# EasyEDA_JamSoft_SI-1_2021-01-22.net
KiCad netlist of a schematic drawn in EasyEDA
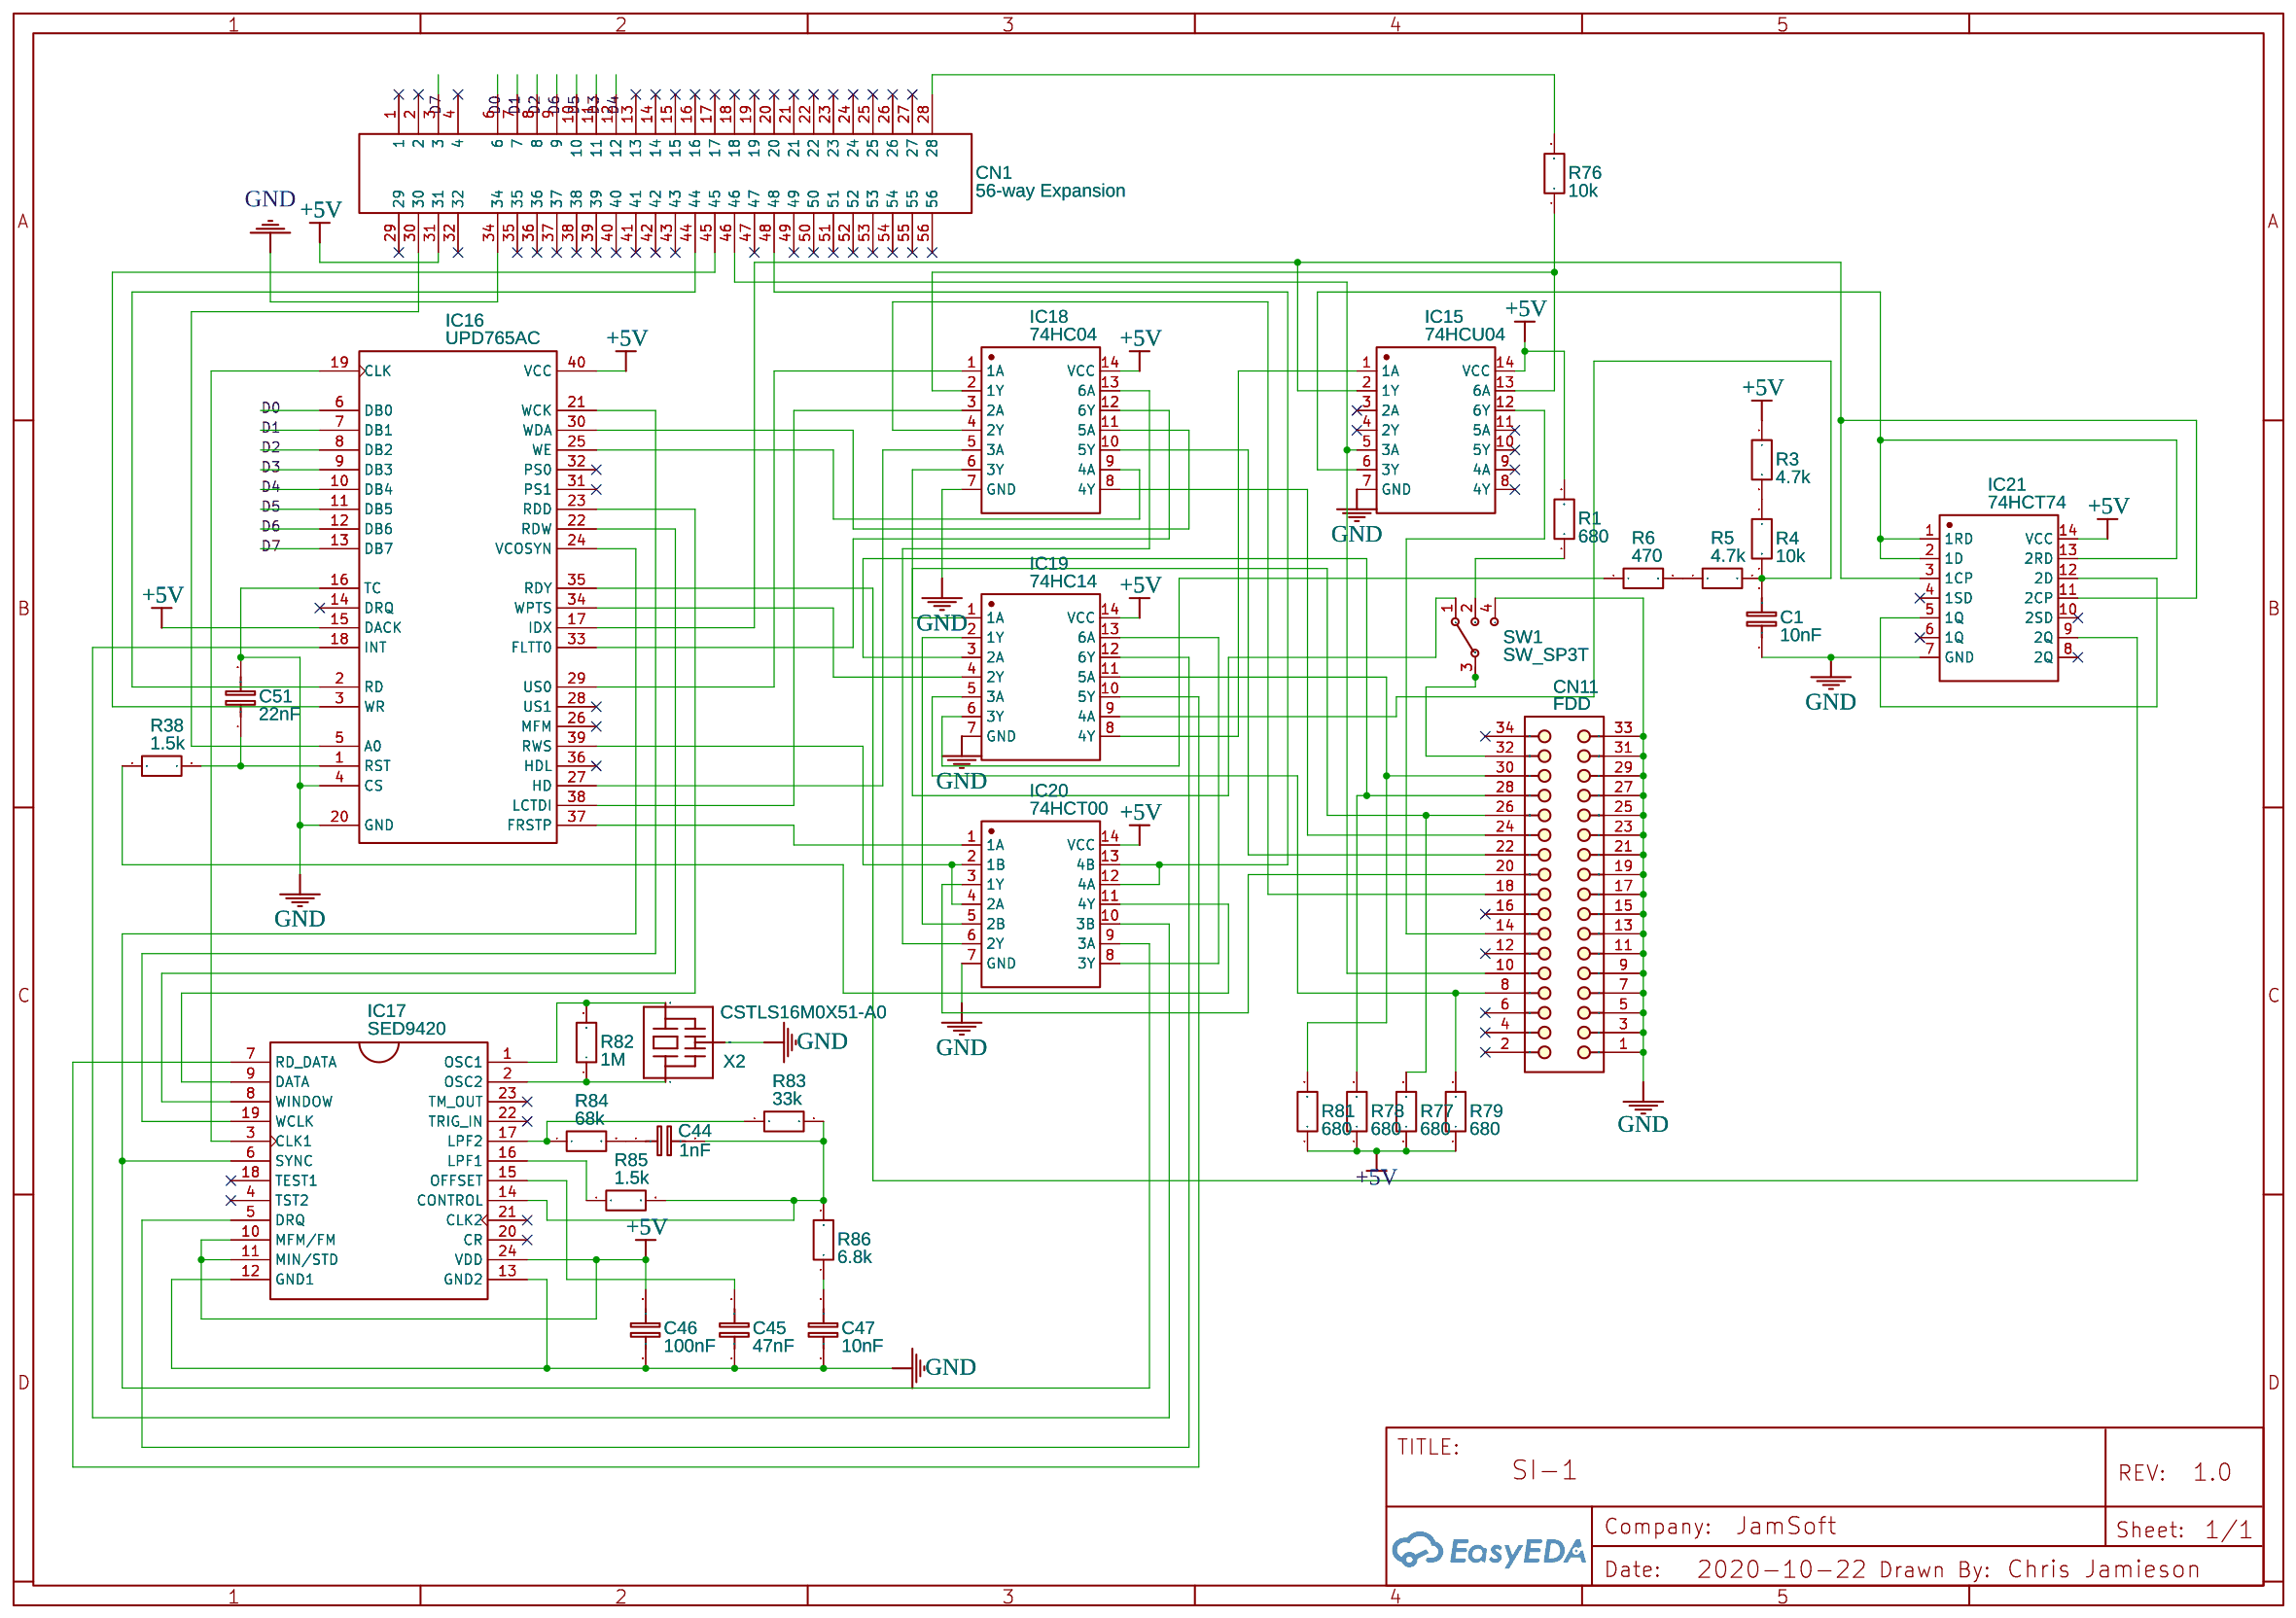
[diagram p0: schematic sheet]

(export (version "E")
  (design (tool "Eeschema 10.0.6"))
  (components
    (comp (ref "C1") (value "10nF") (libsource (lib "") (part "C_RAD-0.2_EU_2")))
    (comp (ref "C44") (value "1nF") (libsource (lib "") (part "C_RAD-0.2_EU")))
    (comp (ref "C45") (value "47nF") (libsource (lib "") (part "C_RAD-0.2_EU_1")))
    (comp (ref "C46") (value "100nF") (libsource (lib "") (part "C_RAD-0.2_EU_1")))
    (comp (ref "C47") (value "10nF") (libsource (lib "") (part "C_RAD-0.2_EU_1")))
    (comp (ref "C51") (value "22nF") (libsource (lib "") (part "C_RAD-0.2_EU_2")))
    (comp (ref "CN1") (value "56-way Expansion") (libsource (lib "") (part "56-way PCB Connector")))
    (comp (ref "CN11") (value "FDD") (libsource (lib "") (part "09 18 534 6914")))
    (comp (ref "IC15") (value "74HCU04") (libsource (lib "") (part "74HC04N,652")))
    (comp (ref "IC16") (value "UPD765AC") (libsource (lib "") (part "UPD765AC")))
    (comp (ref "IC17")
      (value "SED9420")
      (fields (field (name "BOM_Manufacturer Part") "SED9420CAC"))
      (libsource (lib "") (part "SED9420"))
    )
    (comp (ref "IC18") (value "74HC04") (libsource (lib "") (part "74HC04N,652")))
    (comp (ref "IC19") (value "74HC14") (libsource (lib "") (part "74HC14N,652")))
    (comp (ref "IC20") (value "74HCT00") (libsource (lib "") (part "74HCT00N")))
    (comp (ref "IC21") (value "74HCT74") (libsource (lib "") (part "74HCT74N")))
    (comp (ref "R1") (value "680") (libsource (lib "") (part "R_AXIAL-0.4_EU")))
    (comp (ref "R3") (value "4.7k") (libsource (lib "") (part "R_AXIAL-0.4_EU_2")))
    (comp (ref "R4") (value "10k") (libsource (lib "") (part "R_AXIAL-0.4_EU_2")))
    (comp (ref "R5") (value "4.7k") (libsource (lib "") (part "R_AXIAL-0.4_EU_1")))
    (comp (ref "R6") (value "470") (libsource (lib "") (part "R_AXIAL-0.4_EU_1")))
    (comp (ref "R38") (value "1.5k") (libsource (lib "") (part "R_AXIAL-0.4_EU_1")))
    (comp (ref "R76") (value "10k") (libsource (lib "") (part "R_AXIAL-0.4_EU")))
    (comp (ref "R77") (value "680") (libsource (lib "") (part "R_AXIAL-0.4_EU")))
    (comp (ref "R78") (value "680") (libsource (lib "") (part "R_AXIAL-0.4_EU")))
    (comp (ref "R79") (value "680") (libsource (lib "") (part "R_AXIAL-0.4_EU")))
    (comp (ref "R81") (value "680") (libsource (lib "") (part "R_AXIAL-0.4_EU")))
    (comp (ref "R82") (value "1M") (libsource (lib "") (part "R_AXIAL-0.6_EU")))
    (comp (ref "R83") (value "33k") (libsource (lib "") (part "R_AXIAL-0.4_EU_1")))
    (comp (ref "R84") (value "68k") (libsource (lib "") (part "R_AXIAL-0.4_EU_1")))
    (comp (ref "R85") (value "1.5k") (libsource (lib "") (part "R_AXIAL-0.4_EU_1")))
    (comp (ref "R86") (value "6.8k") (libsource (lib "") (part "R_AXIAL-0.4_EU")))
    (comp (ref "SW1") (value "SW_SP3T") (libsource (lib "") (part "SW_SP3T")))
    (comp (ref "X2") (value "CSTLS16M0X51-A0") (libsource (lib "") (part "CSTLS_X")))
  )
  (nets
    (net (code "1") (name "+5V") (class "Default")
      (node (ref "C46") (pin "2") (pinfunction "2_2") (pintype "unspecified"))
      (node (ref "CN1") (pin "31") (pinfunction "31_31") (pintype "unspecified"))
      (node (ref "IC15") (pin "14") (pinfunction "VCC_14") (pintype "unspecified"))
      (node (ref "IC16") (pin "15") (pinfunction "DACK_15") (pintype "unspecified"))
      (node (ref "IC16") (pin "40") (pinfunction "VCC_40") (pintype "passive"))
      (node (ref "IC17") (pin "10") (pinfunction "MFM/FM_10") (pintype "unspecified"))
      (node (ref "IC17") (pin "11") (pinfunction "MIN/STD_11") (pintype "unspecified"))
      (node (ref "IC17") (pin "24") (pinfunction "VDD_24") (pintype "passive"))
      (node (ref "IC18") (pin "14") (pinfunction "VCC_14") (pintype "unspecified"))
      (node (ref "IC19") (pin "14") (pinfunction "VCC_14") (pintype "unspecified"))
      (node (ref "IC20") (pin "14") (pinfunction "VCC_14") (pintype "unspecified"))
      (node (ref "IC21") (pin "14") (pinfunction "VCC_14") (pintype "unspecified"))
      (node (ref "R1") (pin "2") (pinfunction "2_2") (pintype "unspecified"))
      (node (ref "R3") (pin "1") (pinfunction "1_1") (pintype "unspecified"))
      (node (ref "R77") (pin "1") (pinfunction "1_1") (pintype "unspecified"))
      (node (ref "R78") (pin "1") (pinfunction "1_1") (pintype "unspecified"))
      (node (ref "R79") (pin "1") (pinfunction "1_1") (pintype "unspecified"))
      (node (ref "R81") (pin "1") (pinfunction "1_1") (pintype "unspecified"))
    )
    (net (code "2") (name "/D0") (class "Default")
      (node (ref "CN1") (pin "6") (pinfunction "6_6") (pintype "unspecified"))
      (node (ref "IC16") (pin "6") (pinfunction "DB0_6") (pintype "bidirectional"))
    )
    (net (code "3") (name "/D1") (class "Default")
      (node (ref "CN1") (pin "7") (pinfunction "7_7") (pintype "unspecified"))
      (node (ref "IC16") (pin "7") (pinfunction "DB1_7") (pintype "bidirectional"))
    )
    (net (code "4") (name "/D2") (class "Default")
      (node (ref "CN1") (pin "8") (pinfunction "8_8") (pintype "unspecified"))
      (node (ref "IC16") (pin "8") (pinfunction "DB2_8") (pintype "bidirectional"))
    )
    (net (code "5") (name "/D3") (class "Default")
      (node (ref "CN1") (pin "11") (pinfunction "11_11") (pintype "unspecified"))
      (node (ref "IC16") (pin "9") (pinfunction "DB3_9") (pintype "bidirectional"))
    )
    (net (code "6") (name "/D4") (class "Default")
      (node (ref "CN1") (pin "12") (pinfunction "12_12") (pintype "unspecified"))
      (node (ref "IC16") (pin "10") (pinfunction "DB4_10") (pintype "bidirectional"))
    )
    (net (code "7") (name "/D5") (class "Default")
      (node (ref "CN1") (pin "10") (pinfunction "10_10") (pintype "unspecified"))
      (node (ref "IC16") (pin "11") (pinfunction "DB5_11") (pintype "bidirectional"))
    )
    (net (code "8") (name "/D6") (class "Default")
      (node (ref "CN1") (pin "9") (pinfunction "9_9") (pintype "unspecified"))
      (node (ref "IC16") (pin "12") (pinfunction "DB6_12") (pintype "bidirectional"))
    )
    (net (code "9") (name "/D7") (class "Default")
      (node (ref "CN1") (pin "3") (pinfunction "3_3") (pintype "unspecified"))
      (node (ref "IC16") (pin "13") (pinfunction "DB7_13") (pintype "bidirectional"))
    )
    (net (code "10") (name "GND") (class "Default")
      (node (ref "C1") (pin "1") (pinfunction "1_1") (pintype "unspecified"))
      (node (ref "C45") (pin "1") (pinfunction "1_1") (pintype "unspecified"))
      (node (ref "C46") (pin "1") (pinfunction "1_1") (pintype "unspecified"))
      (node (ref "C47") (pin "1") (pinfunction "1_1") (pintype "unspecified"))
      (node (ref "C51") (pin "2") (pinfunction "2_2") (pintype "unspecified"))
      (node (ref "CN1") (pin "34") (pinfunction "34_34") (pintype "unspecified"))
      (node (ref "CN11") (pin "1") (pinfunction "1_1") (pintype "unspecified"))
      (node (ref "CN11") (pin "11") (pinfunction "11_11") (pintype "unspecified"))
      (node (ref "CN11") (pin "13") (pinfunction "13_13") (pintype "unspecified"))
      (node (ref "CN11") (pin "15") (pinfunction "15_15") (pintype "unspecified"))
      (node (ref "CN11") (pin "17") (pinfunction "17_17") (pintype "unspecified"))
      (node (ref "CN11") (pin "19") (pinfunction "19_19") (pintype "unspecified"))
      (node (ref "CN11") (pin "21") (pinfunction "21_21") (pintype "unspecified"))
      (node (ref "CN11") (pin "23") (pinfunction "23_23") (pintype "unspecified"))
      (node (ref "CN11") (pin "25") (pinfunction "25_25") (pintype "unspecified"))
      (node (ref "CN11") (pin "27") (pinfunction "27_27") (pintype "unspecified"))
      (node (ref "CN11") (pin "29") (pinfunction "29_29") (pintype "unspecified"))
      (node (ref "CN11") (pin "3") (pinfunction "3_3") (pintype "unspecified"))
      (node (ref "CN11") (pin "31") (pinfunction "31_31") (pintype "unspecified"))
      (node (ref "CN11") (pin "33") (pinfunction "33_33") (pintype "unspecified"))
      (node (ref "CN11") (pin "5") (pinfunction "5_5") (pintype "unspecified"))
      (node (ref "CN11") (pin "7") (pinfunction "7_7") (pintype "unspecified"))
      (node (ref "CN11") (pin "9") (pinfunction "9_9") (pintype "unspecified"))
      (node (ref "IC15") (pin "7") (pinfunction "GND_7") (pintype "unspecified"))
      (node (ref "IC16") (pin "16") (pinfunction "TC_16") (pintype "unspecified"))
      (node (ref "IC16") (pin "20") (pinfunction "GND_20") (pintype "passive"))
      (node (ref "IC16") (pin "4") (pinfunction "CS_4") (pintype "unspecified"))
      (node (ref "IC17") (pin "12") (pinfunction "GND1_12") (pintype "passive"))
      (node (ref "IC17") (pin "13") (pinfunction "GND2_13") (pintype "passive"))
      (node (ref "IC18") (pin "7") (pinfunction "GND_7") (pintype "unspecified"))
      (node (ref "IC19") (pin "7") (pinfunction "GND_7") (pintype "unspecified"))
      (node (ref "IC20") (pin "7") (pinfunction "GND_7") (pintype "unspecified"))
      (node (ref "IC21") (pin "7") (pinfunction "GND_7") (pintype "unspecified"))
      (node (ref "SW1") (pin "4") (pinfunction "4_4") (pintype "unspecified"))
      (node (ref "X2") (pin "2") (pinfunction "VSS_2") (pintype "passive"))
    )
    (net (code "11") (name "Net-(C44-Pad1)") (class "Default")
      (node (ref "C44") (pin "1") (pinfunction "1_1") (pintype "unspecified"))
      (node (ref "R84") (pin "2") (pinfunction "2_2") (pintype "unspecified"))
    )
    (net (code "12") (name "Net-(C47-Pad2)") (class "Default")
      (node (ref "C47") (pin "2") (pinfunction "2_2") (pintype "unspecified"))
      (node (ref "R86") (pin "1") (pinfunction "1_1") (pintype "unspecified"))
    )
    (net (code "13") (name "Net-(CN1-Pad28)") (class "Default")
      (node (ref "CN1") (pin "28") (pinfunction "28_28") (pintype "unspecified"))
      (node (ref "R76") (pin "2") (pinfunction "2_2") (pintype "unspecified"))
    )
    (net (code "14") (name "Net-(CN11-Pad32)") (class "Default")
      (node (ref "CN11") (pin "32") (pinfunction "32_32") (pintype "unspecified"))
      (node (ref "SW1") (pin "3") (pinfunction "3_3") (pintype "unspecified"))
    )
    (net (code "15") (name "Net-(IC15-1A)") (class "Default")
      (node (ref "IC15") (pin "1") (pinfunction "1A_1") (pintype "unspecified"))
      (node (ref "IC19") (pin "8") (pinfunction "4Y_8") (pintype "unspecified"))
    )
    (net (code "16") (name "Net-(IC15-1Y)") (class "Default")
      (node (ref "IC15") (pin "2") (pinfunction "1Y_2") (pintype "unspecified"))
      (node (ref "IC16") (pin "17") (pinfunction "IDX_17") (pintype "unspecified"))
      (node (ref "IC21") (pin "11") (pinfunction "2CP_11") (pintype "unspecified"))
      (node (ref "IC21") (pin "3") (pinfunction "1CP_3") (pintype "unspecified"))
    )
    (net (code "17") (name "Net-(IC15-3A)") (class "Default")
      (node (ref "CN1") (pin "46") (pinfunction "46_46") (pintype "unspecified"))
      (node (ref "CN11") (pin "10") (pinfunction "10_10") (pintype "unspecified"))
      (node (ref "IC15") (pin "5") (pinfunction "3A_5") (pintype "unspecified"))
    )
    (net (code "18") (name "Net-(IC15-3Y)") (class "Default")
      (node (ref "IC15") (pin "6") (pinfunction "3Y_6") (pintype "unspecified"))
      (node (ref "IC21") (pin "1") (pinfunction "1RD_1") (pintype "unspecified"))
      (node (ref "IC21") (pin "13") (pinfunction "2RD_13") (pintype "unspecified"))
      (node (ref "IC21") (pin "2") (pinfunction "1D_2") (pintype "unspecified"))
    )
    (net (code "19") (name "Net-(IC15-6A)") (class "Default")
      (node (ref "IC15") (pin "13") (pinfunction "6A_13") (pintype "unspecified"))
      (node (ref "IC18") (pin "2") (pinfunction "1Y_2") (pintype "unspecified"))
      (node (ref "R76") (pin "1") (pinfunction "1_1") (pintype "unspecified"))
    )
    (net (code "20") (name "Net-(IC15-6Y)") (class "Default")
      (node (ref "CN11") (pin "14") (pinfunction "14_14") (pintype "unspecified"))
      (node (ref "IC15") (pin "12") (pinfunction "6Y_12") (pintype "unspecified"))
    )
    (net (code "21") (name "Net-(IC16-A0)") (class "Default")
      (node (ref "CN1") (pin "30") (pinfunction "30_30") (pintype "unspecified"))
      (node (ref "IC16") (pin "5") (pinfunction "A0_5") (pintype "unspecified"))
    )
    (net (code "22") (name "Net-(IC16-CLK)") (class "Default")
      (node (ref "IC16") (pin "19") (pinfunction "CLK_19") (pintype "unspecified"))
      (node (ref "IC17") (pin "3") (pinfunction "CLK1_3") (pintype "unspecified"))
    )
    (net (code "23") (name "Net-(IC16-FLTT0)") (class "Default")
      (node (ref "IC16") (pin "33") (pinfunction "FLTT0_33") (pintype "unspecified"))
      (node (ref "IC18") (pin "12") (pinfunction "6Y_12") (pintype "unspecified"))
    )
    (net (code "24") (name "Net-(IC16-FRSTP)") (class "Default")
      (node (ref "IC16") (pin "37") (pinfunction "FRSTP_37") (pintype "output"))
      (node (ref "IC20") (pin "1") (pinfunction "1A_1") (pintype "unspecified"))
    )
    (net (code "25") (name "Net-(IC16-HD)") (class "Default")
      (node (ref "IC16") (pin "27") (pinfunction "HD_27") (pintype "output"))
      (node (ref "IC18") (pin "5") (pinfunction "3A_5") (pintype "unspecified"))
    )
    (net (code "26") (name "Net-(IC16-INT)") (class "Default")
      (node (ref "IC16") (pin "18") (pinfunction "INT_18") (pintype "output"))
      (node (ref "IC20") (pin "10") (pinfunction "3B_10") (pintype "unspecified"))
    )
    (net (code "27") (name "Net-(IC16-LCTDI)") (class "Default")
      (node (ref "IC16") (pin "38") (pinfunction "LCTDI_38") (pintype "output"))
      (node (ref "IC18") (pin "3") (pinfunction "2A_3") (pintype "unspecified"))
    )
    (net (code "28") (name "Net-(IC16-RD)") (class "Default")
      (node (ref "CN1") (pin "44") (pinfunction "44_44") (pintype "unspecified"))
      (node (ref "IC16") (pin "2") (pinfunction "RD_2") (pintype "unspecified"))
    )
    (net (code "29") (name "Net-(IC16-RDD)") (class "Default")
      (node (ref "IC16") (pin "23") (pinfunction "RDD_23") (pintype "unspecified"))
      (node (ref "IC17") (pin "9") (pinfunction "DATA_9") (pintype "unspecified"))
    )
    (net (code "30") (name "Net-(IC16-RDW)") (class "Default")
      (node (ref "IC16") (pin "22") (pinfunction "RDW_22") (pintype "unspecified"))
      (node (ref "IC17") (pin "8") (pinfunction "WINDOW_8") (pintype "unspecified"))
    )
    (net (code "31") (name "Net-(IC16-RDY)") (class "Default")
      (node (ref "IC16") (pin "35") (pinfunction "RDY_35") (pintype "unspecified"))
      (node (ref "IC21") (pin "9") (pinfunction "2Q_9") (pintype "unspecified"))
    )
    (net (code "32") (name "Net-(IC16-RST)") (class "Default")
      (node (ref "C51") (pin "1") (pinfunction "1_1") (pintype "unspecified"))
      (node (ref "IC16") (pin "1") (pinfunction "RST_1") (pintype "unspecified"))
      (node (ref "R38") (pin "2") (pinfunction "2_2") (pintype "unspecified"))
    )
    (net (code "33") (name "Net-(IC16-RWS)") (class "Default")
      (node (ref "IC16") (pin "39") (pinfunction "RWS_39") (pintype "output"))
      (node (ref "IC20") (pin "2") (pinfunction "1B_2") (pintype "unspecified"))
      (node (ref "IC20") (pin "4") (pinfunction "2A_4") (pintype "unspecified"))
    )
    (net (code "34") (name "Net-(IC16-US0)") (class "Default")
      (node (ref "IC16") (pin "29") (pinfunction "US0_29") (pintype "output"))
      (node (ref "IC18") (pin "1") (pinfunction "1A_1") (pintype "unspecified"))
    )
    (net (code "35") (name "Net-(IC16-VCOSYN)") (class "Default")
      (node (ref "IC16") (pin "24") (pinfunction "VCOSYN_24") (pintype "output"))
      (node (ref "IC17") (pin "6") (pinfunction "SYNC_6") (pintype "unspecified"))
      (node (ref "IC20") (pin "9") (pinfunction "3A_9") (pintype "unspecified"))
    )
    (net (code "36") (name "Net-(IC16-WCK)") (class "Default")
      (node (ref "IC16") (pin "21") (pinfunction "WCK_21") (pintype "unspecified"))
      (node (ref "IC17") (pin "19") (pinfunction "WCLK_19") (pintype "unspecified"))
    )
    (net (code "37") (name "Net-(IC16-WDA)") (class "Default")
      (node (ref "IC16") (pin "30") (pinfunction "WDA_30") (pintype "output"))
      (node (ref "IC18") (pin "11") (pinfunction "5A_11") (pintype "unspecified"))
    )
    (net (code "38") (name "Net-(IC16-WE)") (class "Default")
      (node (ref "IC16") (pin "25") (pinfunction "WE_25") (pintype "output"))
      (node (ref "IC18") (pin "9") (pinfunction "4A_9") (pintype "unspecified"))
    )
    (net (code "39") (name "Net-(IC16-WPTS)") (class "Default")
      (node (ref "IC16") (pin "34") (pinfunction "WPTS_34") (pintype "unspecified"))
      (node (ref "IC19") (pin "4") (pinfunction "2Y_4") (pintype "unspecified"))
    )
    (net (code "40") (name "Net-(IC16-WR)") (class "Default")
      (node (ref "CN1") (pin "45") (pinfunction "45_45") (pintype "unspecified"))
      (node (ref "IC16") (pin "3") (pinfunction "WR_3") (pintype "unspecified"))
    )
    (net (code "41") (name "Net-(IC17-CONTROL)") (class "Default")
      (node (ref "C44") (pin "2") (pinfunction "2_2") (pintype "unspecified"))
      (node (ref "IC17") (pin "14") (pinfunction "CONTROL_14") (pintype "unspecified"))
      (node (ref "R83") (pin "2") (pinfunction "2_2") (pintype "unspecified"))
      (node (ref "R85") (pin "2") (pinfunction "2_2") (pintype "unspecified"))
      (node (ref "R86") (pin "2") (pinfunction "2_2") (pintype "unspecified"))
    )
    (net (code "42") (name "Net-(IC17-DRQ)") (class "Default")
      (node (ref "IC17") (pin "5") (pinfunction "DRQ_5") (pintype "unspecified"))
      (node (ref "IC19") (pin "12") (pinfunction "6Y_12") (pintype "unspecified"))
    )
    (net (code "43") (name "Net-(IC17-LPF1)") (class "Default")
      (node (ref "IC17") (pin "16") (pinfunction "LPF1_16") (pintype "unspecified"))
      (node (ref "R85") (pin "1") (pinfunction "1_1") (pintype "unspecified"))
    )
    (net (code "44") (name "Net-(IC17-LPF2)") (class "Default")
      (node (ref "IC17") (pin "17") (pinfunction "LPF2_17") (pintype "unspecified"))
      (node (ref "R83") (pin "1") (pinfunction "1_1") (pintype "unspecified"))
      (node (ref "R84") (pin "1") (pinfunction "1_1") (pintype "unspecified"))
    )
    (net (code "45") (name "Net-(IC17-OFFSET)") (class "Default")
      (node (ref "C45") (pin "2") (pinfunction "2_2") (pintype "unspecified"))
      (node (ref "IC17") (pin "15") (pinfunction "OFFSET_15") (pintype "unspecified"))
    )
    (net (code "46") (name "Net-(IC17-OSC1)") (class "Default")
      (node (ref "IC17") (pin "1") (pinfunction "OSC1_1") (pintype "unspecified"))
      (node (ref "R82") (pin "2") (pinfunction "2_2") (pintype "unspecified"))
      (node (ref "X2") (pin "3") (pinfunction "3_3") (pintype "input"))
    )
    (net (code "47") (name "Net-(IC17-OSC2)") (class "Default")
      (node (ref "IC17") (pin "2") (pinfunction "OSC2_2") (pintype "unspecified"))
      (node (ref "R82") (pin "1") (pinfunction "1_1") (pintype "unspecified"))
      (node (ref "X2") (pin "1") (pinfunction "1_1") (pintype "output"))
    )
    (net (code "48") (name "Net-(IC17-RD_DATA)") (class "Default")
      (node (ref "IC17") (pin "7") (pinfunction "RD_DATA_7") (pintype "unspecified"))
      (node (ref "IC19") (pin "10") (pinfunction "5Y_10") (pintype "unspecified"))
    )
    (net (code "49") (name "Net-(IC18-2Y)") (class "Default")
      (node (ref "CN11") (pin "18") (pinfunction "18_18") (pintype "unspecified"))
      (node (ref "IC18") (pin "4") (pinfunction "2Y_4") (pintype "unspecified"))
    )
    (net (code "50") (name "Net-(IC18-3Y)") (class "Default")
      (node (ref "IC18") (pin "6") (pinfunction "3Y_6") (pintype "unspecified"))
      (node (ref "SW1") (pin "1") (pinfunction "1_1") (pintype "unspecified"))
    )
    (net (code "51") (name "Net-(IC18-4Y)") (class "Default")
      (node (ref "CN11") (pin "24") (pinfunction "24_24") (pintype "unspecified"))
      (node (ref "IC18") (pin "8") (pinfunction "4Y_8") (pintype "unspecified"))
    )
    (net (code "52") (name "Net-(IC18-5Y)") (class "Default")
      (node (ref "CN11") (pin "22") (pinfunction "22_22") (pintype "unspecified"))
      (node (ref "IC18") (pin "10") (pinfunction "5Y_10") (pintype "unspecified"))
    )
    (net (code "53") (name "Net-(IC18-6A)") (class "Default")
      (node (ref "IC18") (pin "13") (pinfunction "6A_13") (pintype "unspecified"))
      (node (ref "IC20") (pin "6") (pinfunction "2Y_6") (pintype "unspecified"))
    )
    (net (code "54") (name "Net-(IC19-1A)") (class "Default")
      (node (ref "CN11") (pin "26") (pinfunction "26_26") (pintype "unspecified"))
      (node (ref "IC19") (pin "1") (pinfunction "1A_1") (pintype "unspecified"))
      (node (ref "R77") (pin "2") (pinfunction "2_2") (pintype "unspecified"))
    )
    (net (code "55") (name "Net-(IC19-1Y)") (class "Default")
      (node (ref "IC19") (pin "2") (pinfunction "1Y_2") (pintype "unspecified"))
      (node (ref "IC20") (pin "5") (pinfunction "2B_5") (pintype "unspecified"))
    )
    (net (code "56") (name "Net-(IC19-2A)") (class "Default")
      (node (ref "CN11") (pin "28") (pinfunction "28_28") (pintype "unspecified"))
      (node (ref "IC19") (pin "3") (pinfunction "2A_3") (pintype "unspecified"))
      (node (ref "R78") (pin "2") (pinfunction "2_2") (pintype "unspecified"))
    )
    (net (code "57") (name "Net-(IC19-3A)") (class "Default")
      (node (ref "CN11") (pin "8") (pinfunction "8_8") (pintype "unspecified"))
      (node (ref "IC19") (pin "5") (pinfunction "3A_5") (pintype "unspecified"))
      (node (ref "R79") (pin "2") (pinfunction "2_2") (pintype "unspecified"))
    )
    (net (code "58") (name "Net-(IC19-3Y)") (class "Default")
      (node (ref "IC19") (pin "6") (pinfunction "3Y_6") (pintype "unspecified"))
      (node (ref "R6") (pin "1") (pinfunction "1_1") (pintype "unspecified"))
    )
    (net (code "59") (name "Net-(IC19-4A)") (class "Default")
      (node (ref "C1") (pin "2") (pinfunction "2_2") (pintype "unspecified"))
      (node (ref "IC19") (pin "9") (pinfunction "4A_9") (pintype "unspecified"))
      (node (ref "R4") (pin "2") (pinfunction "2_2") (pintype "unspecified"))
      (node (ref "R5") (pin "2") (pinfunction "2_2") (pintype "unspecified"))
    )
    (net (code "60") (name "Net-(IC19-5A)") (class "Default")
      (node (ref "CN11") (pin "30") (pinfunction "30_30") (pintype "unspecified"))
      (node (ref "IC19") (pin "11") (pinfunction "5A_11") (pintype "unspecified"))
      (node (ref "R81") (pin "2") (pinfunction "2_2") (pintype "unspecified"))
    )
    (net (code "61") (name "Net-(IC19-6A)") (class "Default")
      (node (ref "IC19") (pin "13") (pinfunction "6A_13") (pintype "unspecified"))
      (node (ref "IC20") (pin "8") (pinfunction "3Y_8") (pintype "unspecified"))
    )
    (net (code "62") (name "Net-(IC20-1Y)") (class "Default")
      (node (ref "CN11") (pin "20") (pinfunction "20_20") (pintype "unspecified"))
      (node (ref "IC20") (pin "3") (pinfunction "1Y_3") (pintype "unspecified"))
    )
    (net (code "63") (name "Net-(IC20-4A)") (class "Default")
      (node (ref "CN1") (pin "48") (pinfunction "48_48") (pintype "unspecified"))
      (node (ref "IC20") (pin "12") (pinfunction "4A_12") (pintype "unspecified"))
      (node (ref "IC20") (pin "13") (pinfunction "4B_13") (pintype "unspecified"))
    )
    (net (code "64") (name "Net-(IC20-4Y)") (class "Default")
      (node (ref "IC20") (pin "11") (pinfunction "4Y_11") (pintype "unspecified"))
      (node (ref "R38") (pin "1") (pinfunction "1_1") (pintype "unspecified"))
    )
    (net (code "65") (name "Net-(IC21-2D)") (class "Default")
      (node (ref "IC21") (pin "12") (pinfunction "2D_12") (pintype "unspecified"))
      (node (ref "IC21") (pin "5") (pinfunction "1Q_5") (pintype "unspecified"))
    )
    (net (code "66") (name "Net-(R1-Pad1)") (class "Default")
      (node (ref "R1") (pin "1") (pinfunction "1_1") (pintype "unspecified"))
      (node (ref "SW1") (pin "2") (pinfunction "2_2") (pintype "unspecified"))
    )
    (net (code "67") (name "Net-(R3-Pad2)") (class "Default")
      (node (ref "R3") (pin "2") (pinfunction "2_2") (pintype "unspecified"))
      (node (ref "R4") (pin "1") (pinfunction "1_1") (pintype "unspecified"))
    )
    (net (code "68") (name "Net-(R5-Pad1)") (class "Default")
      (node (ref "R5") (pin "1") (pinfunction "1_1") (pintype "unspecified"))
      (node (ref "R6") (pin "2") (pinfunction "2_2") (pintype "unspecified"))
    )
    (net (code "69") (name "unconnected-(CN1-Pad1)") (class "Default")
      (node (ref "CN1") (pin "1") (pinfunction "1_1") (pintype "unspecified+no_connect"))
    )
    (net (code "70") (name "unconnected-(CN1-Pad2)") (class "Default")
      (node (ref "CN1") (pin "2") (pinfunction "2_2") (pintype "unspecified+no_connect"))
    )
    (net (code "71") (name "unconnected-(CN1-Pad4)") (class "Default")
      (node (ref "CN1") (pin "4") (pinfunction "4_4") (pintype "unspecified+no_connect"))
    )
    (net (code "72") (name "unconnected-(CN1-Pad13)") (class "Default")
      (node (ref "CN1") (pin "13") (pinfunction "13_13") (pintype "unspecified+no_connect"))
    )
    (net (code "73") (name "unconnected-(CN1-Pad14)") (class "Default")
      (node (ref "CN1") (pin "14") (pinfunction "14_14") (pintype "unspecified+no_connect"))
    )
    (net (code "74") (name "unconnected-(CN1-Pad15)") (class "Default")
      (node (ref "CN1") (pin "15") (pinfunction "15_15") (pintype "unspecified+no_connect"))
    )
    (net (code "75") (name "unconnected-(CN1-Pad16)") (class "Default")
      (node (ref "CN1") (pin "16") (pinfunction "16_16") (pintype "unspecified+no_connect"))
    )
    (net (code "76") (name "unconnected-(CN1-Pad17)") (class "Default")
      (node (ref "CN1") (pin "17") (pinfunction "17_17") (pintype "unspecified+no_connect"))
    )
    (net (code "77") (name "unconnected-(CN1-Pad18)") (class "Default")
      (node (ref "CN1") (pin "18") (pinfunction "18_18") (pintype "unspecified+no_connect"))
    )
    (net (code "78") (name "unconnected-(CN1-Pad19)") (class "Default")
      (node (ref "CN1") (pin "19") (pinfunction "19_19") (pintype "unspecified+no_connect"))
    )
    (net (code "79") (name "unconnected-(CN1-Pad20)") (class "Default")
      (node (ref "CN1") (pin "20") (pinfunction "20_20") (pintype "unspecified+no_connect"))
    )
    (net (code "80") (name "unconnected-(CN1-Pad21)") (class "Default")
      (node (ref "CN1") (pin "21") (pinfunction "21_21") (pintype "unspecified+no_connect"))
    )
    (net (code "81") (name "unconnected-(CN1-Pad22)") (class "Default")
      (node (ref "CN1") (pin "22") (pinfunction "22_22") (pintype "unspecified+no_connect"))
    )
    (net (code "82") (name "unconnected-(CN1-Pad23)") (class "Default")
      (node (ref "CN1") (pin "23") (pinfunction "23_23") (pintype "unspecified+no_connect"))
    )
    (net (code "83") (name "unconnected-(CN1-Pad24)") (class "Default")
      (node (ref "CN1") (pin "24") (pinfunction "24_24") (pintype "unspecified+no_connect"))
    )
    (net (code "84") (name "unconnected-(CN1-Pad25)") (class "Default")
      (node (ref "CN1") (pin "25") (pinfunction "25_25") (pintype "unspecified+no_connect"))
    )
    (net (code "85") (name "unconnected-(CN1-Pad26)") (class "Default")
      (node (ref "CN1") (pin "26") (pinfunction "26_26") (pintype "unspecified+no_connect"))
    )
    (net (code "86") (name "unconnected-(CN1-Pad27)") (class "Default")
      (node (ref "CN1") (pin "27") (pinfunction "27_27") (pintype "unspecified+no_connect"))
    )
    (net (code "87") (name "unconnected-(CN1-Pad29)") (class "Default")
      (node (ref "CN1") (pin "29") (pinfunction "29_29") (pintype "unspecified+no_connect"))
    )
    (net (code "88") (name "unconnected-(CN1-Pad32)") (class "Default")
      (node (ref "CN1") (pin "32") (pinfunction "32_32") (pintype "unspecified+no_connect"))
    )
    (net (code "89") (name "unconnected-(CN1-Pad35)") (class "Default")
      (node (ref "CN1") (pin "35") (pinfunction "35_35") (pintype "unspecified+no_connect"))
    )
    (net (code "90") (name "unconnected-(CN1-Pad36)") (class "Default")
      (node (ref "CN1") (pin "36") (pinfunction "36_36") (pintype "unspecified+no_connect"))
    )
    (net (code "91") (name "unconnected-(CN1-Pad37)") (class "Default")
      (node (ref "CN1") (pin "37") (pinfunction "37_37") (pintype "unspecified+no_connect"))
    )
    (net (code "92") (name "unconnected-(CN1-Pad38)") (class "Default")
      (node (ref "CN1") (pin "38") (pinfunction "38_38") (pintype "unspecified+no_connect"))
    )
    (net (code "93") (name "unconnected-(CN1-Pad39)") (class "Default")
      (node (ref "CN1") (pin "39") (pinfunction "39_39") (pintype "unspecified+no_connect"))
    )
    (net (code "94") (name "unconnected-(CN1-Pad40)") (class "Default")
      (node (ref "CN1") (pin "40") (pinfunction "40_40") (pintype "unspecified+no_connect"))
    )
    (net (code "95") (name "unconnected-(CN1-Pad41)") (class "Default")
      (node (ref "CN1") (pin "41") (pinfunction "41_41") (pintype "unspecified+no_connect"))
    )
    (net (code "96") (name "unconnected-(CN1-Pad42)") (class "Default")
      (node (ref "CN1") (pin "42") (pinfunction "42_42") (pintype "unspecified+no_connect"))
    )
    (net (code "97") (name "unconnected-(CN1-Pad43)") (class "Default")
      (node (ref "CN1") (pin "43") (pinfunction "43_43") (pintype "unspecified+no_connect"))
    )
    (net (code "98") (name "unconnected-(CN1-Pad47)") (class "Default")
      (node (ref "CN1") (pin "47") (pinfunction "47_47") (pintype "unspecified+no_connect"))
    )
    (net (code "99") (name "unconnected-(CN1-Pad49)") (class "Default")
      (node (ref "CN1") (pin "49") (pinfunction "49_49") (pintype "unspecified+no_connect"))
    )
    (net (code "100") (name "unconnected-(CN1-Pad50)") (class "Default")
      (node (ref "CN1") (pin "50") (pinfunction "50_50") (pintype "unspecified+no_connect"))
    )
    (net (code "101") (name "unconnected-(CN1-Pad51)") (class "Default")
      (node (ref "CN1") (pin "51") (pinfunction "51_51") (pintype "unspecified+no_connect"))
    )
    (net (code "102") (name "unconnected-(CN1-Pad52)") (class "Default")
      (node (ref "CN1") (pin "52") (pinfunction "52_52") (pintype "unspecified+no_connect"))
    )
    (net (code "103") (name "unconnected-(CN1-Pad53)") (class "Default")
      (node (ref "CN1") (pin "53") (pinfunction "53_53") (pintype "unspecified+no_connect"))
    )
    (net (code "104") (name "unconnected-(CN1-Pad54)") (class "Default")
      (node (ref "CN1") (pin "54") (pinfunction "54_54") (pintype "unspecified+no_connect"))
    )
    (net (code "105") (name "unconnected-(CN1-Pad55)") (class "Default")
      (node (ref "CN1") (pin "55") (pinfunction "55_55") (pintype "unspecified+no_connect"))
    )
    (net (code "106") (name "unconnected-(CN1-Pad56)") (class "Default")
      (node (ref "CN1") (pin "56") (pinfunction "56_56") (pintype "unspecified+no_connect"))
    )
    (net (code "107") (name "unconnected-(CN11-Pad2)") (class "Default")
      (node (ref "CN11") (pin "2") (pinfunction "2_2") (pintype "unspecified+no_connect"))
    )
    (net (code "108") (name "unconnected-(CN11-Pad4)") (class "Default")
      (node (ref "CN11") (pin "4") (pinfunction "4_4") (pintype "unspecified+no_connect"))
    )
    (net (code "109") (name "unconnected-(CN11-Pad6)") (class "Default")
      (node (ref "CN11") (pin "6") (pinfunction "6_6") (pintype "unspecified+no_connect"))
    )
    (net (code "110") (name "unconnected-(CN11-Pad12)") (class "Default")
      (node (ref "CN11") (pin "12") (pinfunction "12_12") (pintype "unspecified+no_connect"))
    )
    (net (code "111") (name "unconnected-(CN11-Pad16)") (class "Default")
      (node (ref "CN11") (pin "16") (pinfunction "16_16") (pintype "unspecified+no_connect"))
    )
    (net (code "112") (name "unconnected-(CN11-Pad34)") (class "Default")
      (node (ref "CN11") (pin "34") (pinfunction "34_34") (pintype "unspecified+no_connect"))
    )
    (net (code "113") (name "unconnected-(IC15-2A-Pad3)") (class "Default")
      (node (ref "IC15") (pin "3") (pinfunction "2A_3") (pintype "unspecified+no_connect"))
    )
    (net (code "114") (name "unconnected-(IC15-2Y-Pad4)") (class "Default")
      (node (ref "IC15") (pin "4") (pinfunction "2Y_4") (pintype "unspecified+no_connect"))
    )
    (net (code "115") (name "unconnected-(IC15-4A-Pad9)") (class "Default")
      (node (ref "IC15") (pin "9") (pinfunction "4A_9") (pintype "unspecified+no_connect"))
    )
    (net (code "116") (name "unconnected-(IC15-4Y-Pad8)") (class "Default")
      (node (ref "IC15") (pin "8") (pinfunction "4Y_8") (pintype "unspecified+no_connect"))
    )
    (net (code "117") (name "unconnected-(IC15-5A-Pad11)") (class "Default")
      (node (ref "IC15") (pin "11") (pinfunction "5A_11") (pintype "unspecified+no_connect"))
    )
    (net (code "118") (name "unconnected-(IC15-5Y-Pad10)") (class "Default")
      (node (ref "IC15") (pin "10") (pinfunction "5Y_10") (pintype "unspecified+no_connect"))
    )
    (net (code "119") (name "unconnected-(IC16-DRQ-Pad14)") (class "Default")
      (node (ref "IC16") (pin "14") (pinfunction "DRQ_14") (pintype "output+no_connect"))
    )
    (net (code "120") (name "unconnected-(IC16-HDL-Pad36)") (class "Default")
      (node (ref "IC16") (pin "36") (pinfunction "HDL_36") (pintype "output+no_connect"))
    )
    (net (code "121") (name "unconnected-(IC16-MFM-Pad26)") (class "Default")
      (node (ref "IC16") (pin "26") (pinfunction "MFM_26") (pintype "output+no_connect"))
    )
    (net (code "122") (name "unconnected-(IC16-PS0-Pad32)") (class "Default")
      (node (ref "IC16") (pin "32") (pinfunction "PS0_32") (pintype "output+no_connect"))
    )
    (net (code "123") (name "unconnected-(IC16-PS1-Pad31)") (class "Default")
      (node (ref "IC16") (pin "31") (pinfunction "PS1_31") (pintype "output+no_connect"))
    )
    (net (code "124") (name "unconnected-(IC16-US1-Pad28)") (class "Default")
      (node (ref "IC16") (pin "28") (pinfunction "US1_28") (pintype "output+no_connect"))
    )
    (net (code "125") (name "unconnected-(IC17-CLK2-Pad21)") (class "Default")
      (node (ref "IC17") (pin "21") (pinfunction "CLK2_21") (pintype "unspecified+no_connect"))
    )
    (net (code "126") (name "unconnected-(IC17-CR-Pad20)") (class "Default")
      (node (ref "IC17") (pin "20") (pinfunction "CR_20") (pintype "unspecified+no_connect"))
    )
    (net (code "127") (name "unconnected-(IC17-TEST1-Pad18)") (class "Default")
      (node (ref "IC17") (pin "18") (pinfunction "TEST1_18") (pintype "unspecified+no_connect"))
    )
    (net (code "128") (name "unconnected-(IC17-TM_OUT-Pad23)") (class "Default")
      (node (ref "IC17") (pin "23") (pinfunction "TM_OUT_23") (pintype "unspecified+no_connect"))
    )
    (net (code "129") (name "unconnected-(IC17-TRIG_IN-Pad22)") (class "Default")
      (node (ref "IC17") (pin "22") (pinfunction "TRIG_IN_22") (pintype "unspecified+no_connect"))
    )
    (net (code "130") (name "unconnected-(IC17-TST2-Pad4)") (class "Default")
      (node (ref "IC17") (pin "4") (pinfunction "TST2_4") (pintype "unspecified+no_connect"))
    )
    (net (code "131") (name "unconnected-(IC21-1Q-Pad6)") (class "Default")
      (node (ref "IC21") (pin "6") (pinfunction "1Q_6") (pintype "unspecified+no_connect"))
    )
    (net (code "132") (name "unconnected-(IC21-1SD-Pad4)") (class "Default")
      (node (ref "IC21") (pin "4") (pinfunction "1SD_4") (pintype "unspecified+no_connect"))
    )
    (net (code "133") (name "unconnected-(IC21-2Q-Pad8)") (class "Default")
      (node (ref "IC21") (pin "8") (pinfunction "2Q_8") (pintype "unspecified+no_connect"))
    )
    (net (code "134") (name "unconnected-(IC21-2SD-Pad10)") (class "Default")
      (node (ref "IC21") (pin "10") (pinfunction "2SD_10") (pintype "unspecified+no_connect"))
    )
  )
)
